# two_tone__1.net
KiCad netlist of a schematic drawn in EAGLE
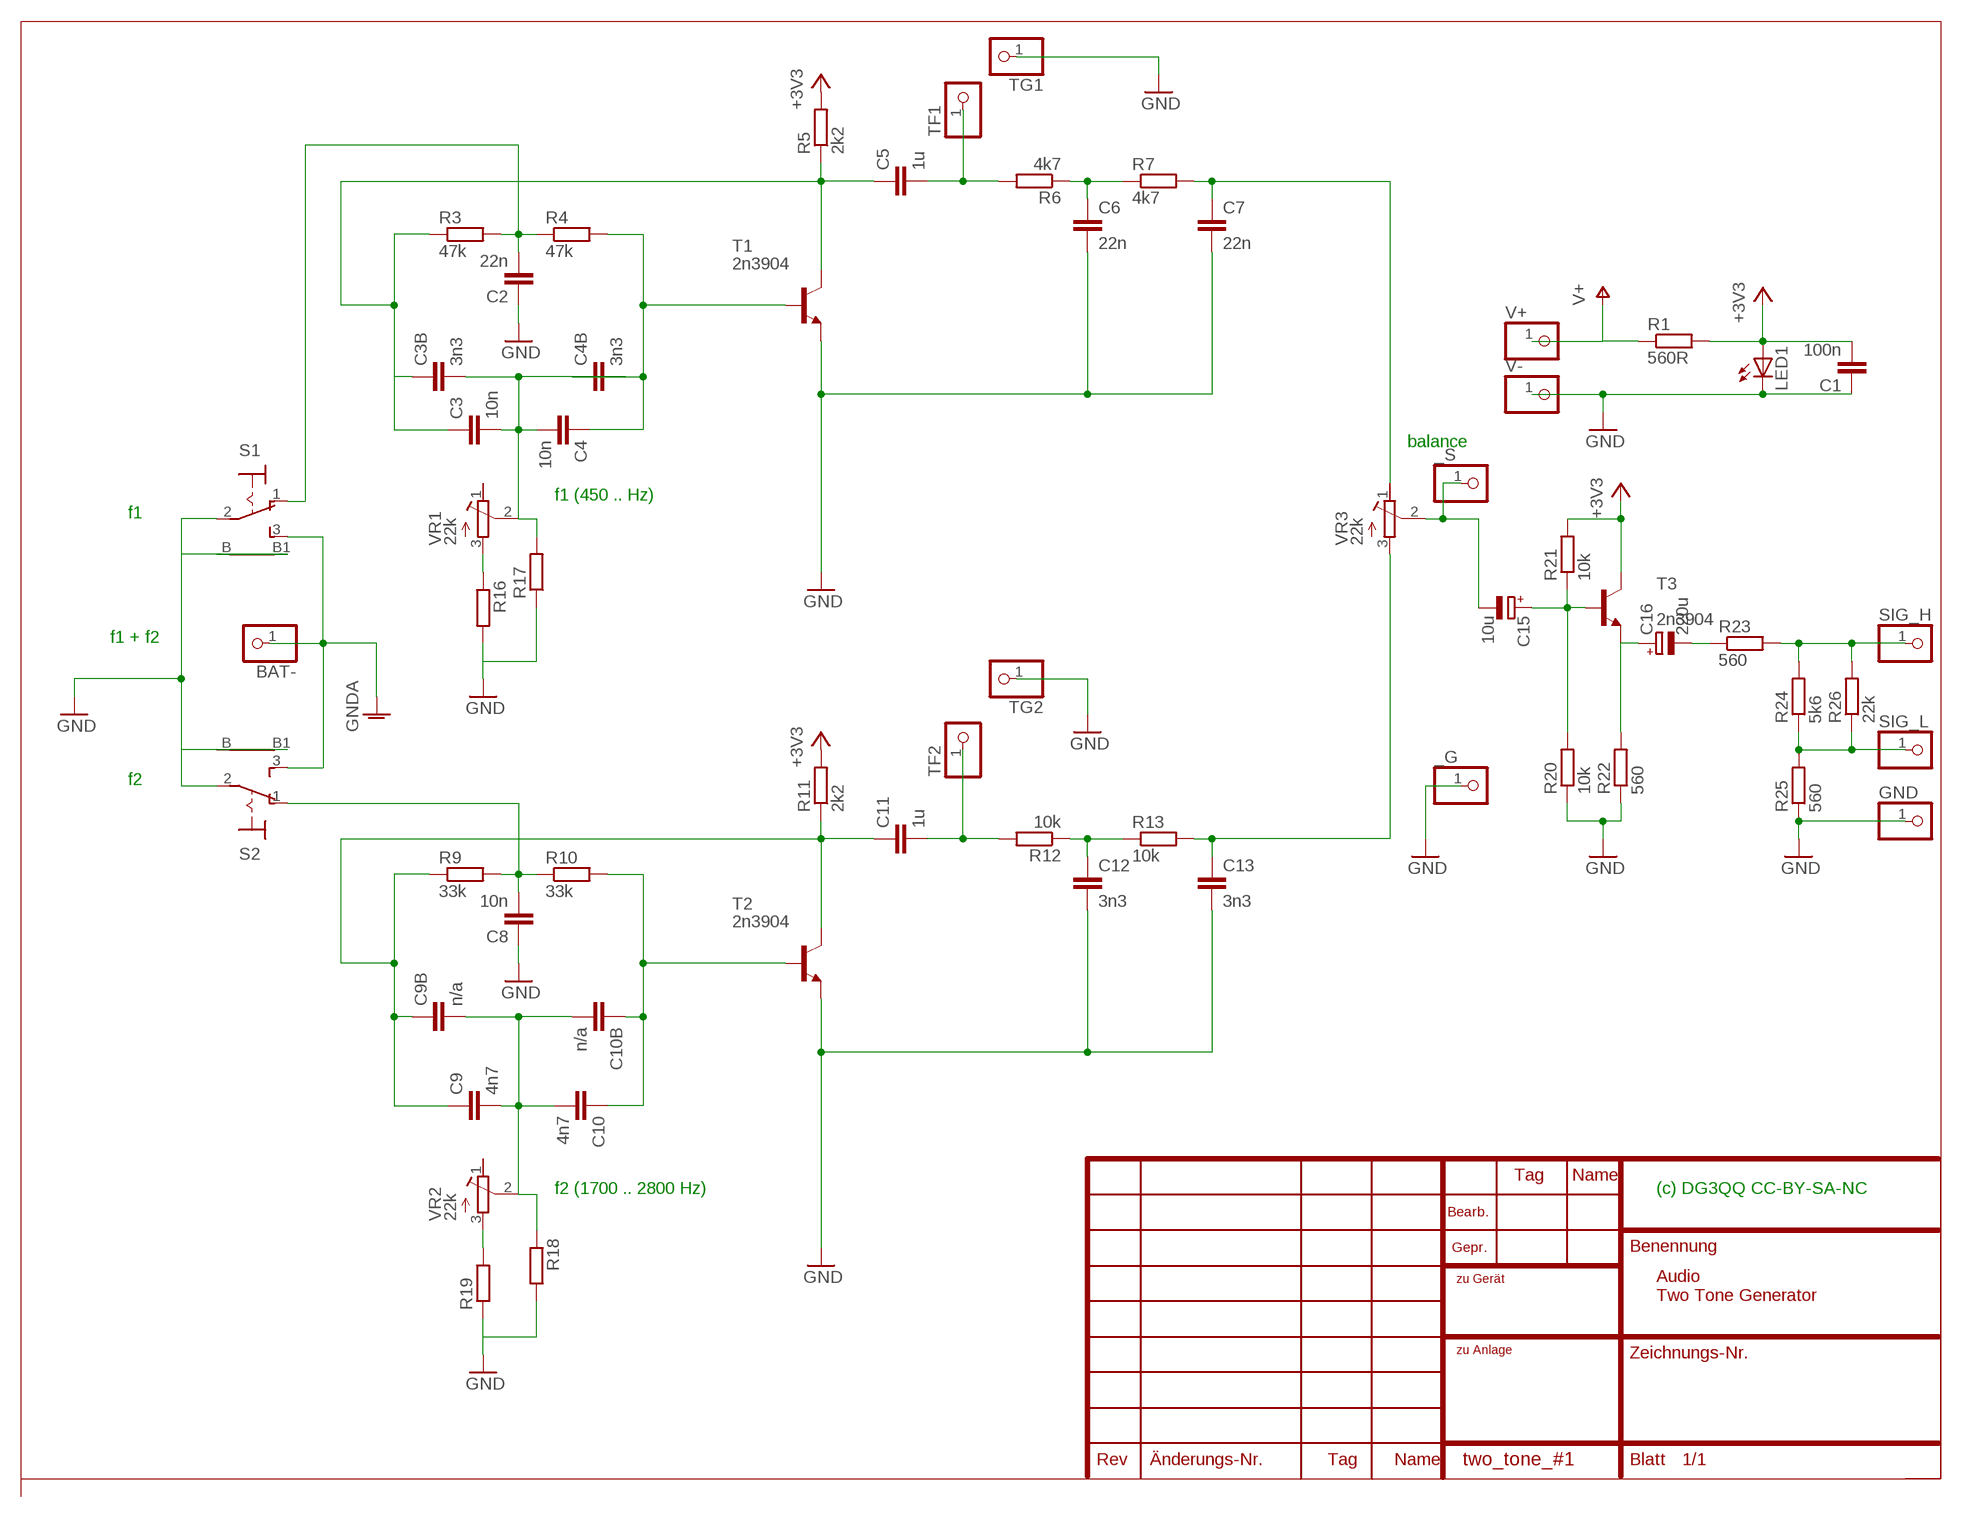
[diagram p0: schematic, sheet 1]

(export (version "E")
  (design (tool "Eeschema 10.0.6"))
  (components
    (comp (ref "BAT-")
      (value "PINHD-1X1")
      (footprint "eagle-import:1X01")
      (libsource (lib "eagle-import") (part "PINHD-1X1"))
    )
    (comp (ref "C1")
      (value "100n")
      (footprint "eagle-import:C025_050-025X075")
      (libsource (lib "eagle-import") (part "C-EU025_050-025X075"))
    )
    (comp (ref "C2")
      (value "22n")
      (footprint "eagle-import:C025_050-025X075")
      (libsource (lib "eagle-import") (part "C-EU025_050-025X075"))
    )
    (comp (ref "C3")
      (value "10n")
      (footprint "eagle-import:C025_050-025X075")
      (libsource (lib "eagle-import") (part "C-EU025_050-025X075"))
    )
    (comp (ref "C3B")
      (value "3n3")
      (footprint "eagle-import:C025_050-025X075")
      (libsource (lib "eagle-import") (part "C-EU025_050-025X075"))
    )
    (comp (ref "C4")
      (value "10n")
      (footprint "eagle-import:C025_050-025X075")
      (libsource (lib "eagle-import") (part "C-EU025_050-025X075"))
    )
    (comp (ref "C4B")
      (value "3n3")
      (footprint "eagle-import:C025_050-025X075")
      (libsource (lib "eagle-import") (part "C-EU025_050-025X075"))
    )
    (comp (ref "C5")
      (value "1u")
      (footprint "eagle-import:C025_050-025X075")
      (libsource (lib "eagle-import") (part "C-EU025_050-025X075"))
    )
    (comp (ref "C6")
      (value "22n")
      (footprint "eagle-import:C025_050-025X075")
      (libsource (lib "eagle-import") (part "C-EU025_050-025X075"))
    )
    (comp (ref "C7")
      (value "22n")
      (footprint "eagle-import:C025_050-025X075")
      (libsource (lib "eagle-import") (part "C-EU025_050-025X075"))
    )
    (comp (ref "C8")
      (value "10n")
      (footprint "eagle-import:C025_050-025X075")
      (libsource (lib "eagle-import") (part "C-EU025_050-025X075"))
    )
    (comp (ref "C9")
      (value "4n7")
      (footprint "eagle-import:C025_050-025X075")
      (libsource (lib "eagle-import") (part "C-EU025_050-025X075"))
    )
    (comp (ref "C9B")
      (value "n/a")
      (footprint "eagle-import:C025_050-025X075")
      (libsource (lib "eagle-import") (part "C-EU025_050-025X075"))
    )
    (comp (ref "C10")
      (value "4n7")
      (footprint "eagle-import:C025_050-025X075")
      (libsource (lib "eagle-import") (part "C-EU025_050-025X075"))
    )
    (comp (ref "C10B")
      (value "n/a")
      (footprint "eagle-import:C025_050-025X075")
      (libsource (lib "eagle-import") (part "C-EU025_050-025X075"))
    )
    (comp (ref "C11")
      (value "1u")
      (footprint "eagle-import:C025_050-025X075")
      (libsource (lib "eagle-import") (part "C-EU025_050-025X075"))
    )
    (comp (ref "C12")
      (value "3n3")
      (footprint "eagle-import:C025_050-025X075")
      (libsource (lib "eagle-import") (part "C-EU025_050-025X075"))
    )
    (comp (ref "C13")
      (value "3n3")
      (footprint "eagle-import:C025_050-025X075")
      (libsource (lib "eagle-import") (part "C-EU025_050-025X075"))
    )
    (comp (ref "C15")
      (value "10u")
      (footprint "eagle-import:E2,5-5")
      (libsource (lib "eagle-import") (part "CPOL-EUE2.5-5"))
    )
    (comp (ref "C16")
      (value "220u")
      (footprint "eagle-import:E5-10,5")
      (libsource (lib "eagle-import") (part "CPOL-EUE5-10.5"))
    )
    (comp (ref "GND")
      (value "PINHD-1X1")
      (footprint "eagle-import:1X01")
      (libsource (lib "eagle-import") (part "PINHD-1X1"))
    )
    (comp (ref "LED1")
      (value "LED3MM")
      (footprint "eagle-import:LED3MM")
      (libsource (lib "eagle-import") (part "LED3MM"))
    )
    (comp (ref "R1")
      (value "560R")
      (footprint "eagle-import:0207_2V")
      (libsource (lib "eagle-import") (part "R-EU_0207/2V"))
    )
    (comp (ref "R3")
      (value "47k")
      (footprint "eagle-import:0207_10")
      (libsource (lib "eagle-import") (part "R-EU_0207/10"))
    )
    (comp (ref "R4")
      (value "47k")
      (footprint "eagle-import:0207_2V")
      (libsource (lib "eagle-import") (part "R-EU_0207/2V"))
    )
    (comp (ref "R5")
      (value "2k2")
      (footprint "eagle-import:0207_2V")
      (libsource (lib "eagle-import") (part "R-EU_0207/2V"))
    )
    (comp (ref "R6")
      (value "4k7")
      (footprint "eagle-import:0207_2V")
      (libsource (lib "eagle-import") (part "R-EU_0207/2V"))
    )
    (comp (ref "R7")
      (value "4k7")
      (footprint "eagle-import:0207_2V")
      (libsource (lib "eagle-import") (part "R-EU_0207/2V"))
    )
    (comp (ref "R9")
      (value "33k")
      (footprint "eagle-import:0207_10")
      (libsource (lib "eagle-import") (part "R-EU_0207/10"))
    )
    (comp (ref "R10")
      (value "33k")
      (footprint "eagle-import:0207_2V")
      (libsource (lib "eagle-import") (part "R-EU_0207/2V"))
    )
    (comp (ref "R11")
      (value "2k2")
      (footprint "eagle-import:0207_2V")
      (libsource (lib "eagle-import") (part "R-EU_0207/2V"))
    )
    (comp (ref "R12")
      (value "10k")
      (footprint "eagle-import:0207_2V")
      (libsource (lib "eagle-import") (part "R-EU_0207/2V"))
    )
    (comp (ref "R13")
      (value "10k")
      (footprint "eagle-import:0207_2V")
      (libsource (lib "eagle-import") (part "R-EU_0207/2V"))
    )
    (comp (ref "R16")
      (value "R-EU_0207/2V")
      (footprint "eagle-import:0207_2V")
      (libsource (lib "eagle-import") (part "R-EU_0207/2V"))
    )
    (comp (ref "R17")
      (value "R-EU_0207/2V")
      (footprint "eagle-import:0207_2V")
      (libsource (lib "eagle-import") (part "R-EU_0207/2V"))
    )
    (comp (ref "R18")
      (value "R-EU_0207/2V")
      (footprint "eagle-import:0207_2V")
      (libsource (lib "eagle-import") (part "R-EU_0207/2V"))
    )
    (comp (ref "R19")
      (value "R-EU_0207/2V")
      (footprint "eagle-import:0207_2V")
      (libsource (lib "eagle-import") (part "R-EU_0207/2V"))
    )
    (comp (ref "R20")
      (value "10k")
      (footprint "eagle-import:0207_2V")
      (libsource (lib "eagle-import") (part "R-EU_0207/2V"))
    )
    (comp (ref "R21")
      (value "10k")
      (footprint "eagle-import:0207_2V")
      (libsource (lib "eagle-import") (part "R-EU_0207/2V"))
    )
    (comp (ref "R22")
      (value "560")
      (footprint "eagle-import:0207_2V")
      (libsource (lib "eagle-import") (part "R-EU_0207/2V"))
    )
    (comp (ref "R23")
      (value "560")
      (footprint "eagle-import:0207_2V")
      (libsource (lib "eagle-import") (part "R-EU_0207/2V"))
    )
    (comp (ref "R24")
      (value "5k6")
      (footprint "eagle-import:0207_2V")
      (libsource (lib "eagle-import") (part "R-EU_0207/2V"))
    )
    (comp (ref "R25")
      (value "560")
      (footprint "eagle-import:0207_2V")
      (libsource (lib "eagle-import") (part "R-EU_0207/2V"))
    )
    (comp (ref "R26")
      (value "22k")
      (footprint "eagle-import:0207_2V")
      (libsource (lib "eagle-import") (part "R-EU_0207/2V"))
    )
    (comp (ref "S1")
      (value "9070-1W")
      (footprint "eagle-import:9070-1W")
      (libsource (lib "eagle-import") (part "9070-1W"))
    )
    (comp (ref "S2")
      (value "9070-1W")
      (footprint "eagle-import:9070-1W")
      (libsource (lib "eagle-import") (part "9070-1W"))
    )
    (comp (ref "SIG_H")
      (value "PINHD-1X1")
      (footprint "eagle-import:1X01")
      (libsource (lib "eagle-import") (part "PINHD-1X1"))
    )
    (comp (ref "SIG_L")
      (value "PINHD-1X1")
      (footprint "eagle-import:1X01")
      (libsource (lib "eagle-import") (part "PINHD-1X1"))
    )
    (comp (ref "T1")
      (value "2n3904")
      (footprint "eagle-import:TO92-EBC")
      (libsource (lib "eagle-import") (part "-NPN-TO92-EBC2N3904"))
    )
    (comp (ref "T2")
      (value "2n3904")
      (footprint "eagle-import:TO92-EBC")
      (libsource (lib "eagle-import") (part "-NPN-TO92-EBC2N3904"))
    )
    (comp (ref "T3")
      (value "2n3904")
      (footprint "eagle-import:TO92-EBC")
      (libsource (lib "eagle-import") (part "-NPN-TO92-EBC2N3904"))
    )
    (comp (ref "TF1")
      (value "PINHD-1X1")
      (footprint "eagle-import:1X01")
      (libsource (lib "eagle-import") (part "PINHD-1X1"))
    )
    (comp (ref "TF2")
      (value "PINHD-1X1")
      (footprint "eagle-import:1X01")
      (libsource (lib "eagle-import") (part "PINHD-1X1"))
    )
    (comp (ref "TG1")
      (value "PINHD-1X1")
      (footprint "eagle-import:1X01")
      (libsource (lib "eagle-import") (part "PINHD-1X1"))
    )
    (comp (ref "TG2")
      (value "PINHD-1X1")
      (footprint "eagle-import:1X01")
      (libsource (lib "eagle-import") (part "PINHD-1X1"))
    )
    (comp (ref "V+")
      (value "PINHD-1X1")
      (footprint "eagle-import:1X01")
      (libsource (lib "eagle-import") (part "PINHD-1X1"))
    )
    (comp (ref "V-")
      (value "PINHD-1X1")
      (footprint "eagle-import:1X01")
      (libsource (lib "eagle-import") (part "PINHD-1X1"))
    )
    (comp (ref "VR1")
      (value "22k")
      (footprint "eagle-import:SPINDLE_414S6")
      (libsource (lib "eagle-import") (part "R-TRIMM_414S6"))
    )
    (comp (ref "VR2")
      (value "22k")
      (footprint "eagle-import:SPINDLE_414S6")
      (libsource (lib "eagle-import") (part "R-TRIMM_414S6"))
    )
    (comp (ref "VR3")
      (value "22k")
      (footprint "eagle-import:SPINDLE_414S6")
      (libsource (lib "eagle-import") (part "R-TRIMM_414S6"))
    )
    (comp (ref "_G")
      (value "PINHD-1X1")
      (footprint "eagle-import:1X01")
      (libsource (lib "eagle-import") (part "PINHD-1X1"))
    )
    (comp (ref "_S")
      (value "PINHD-1X1")
      (footprint "eagle-import:1X01")
      (libsource (lib "eagle-import") (part "PINHD-1X1"))
    )
  )
  (nets
    (net (code "1") (name "+3V3") (class "Default")
      (node (ref "C1") (pin "2") (pinfunction "2_2") (pintype "passive"))
      (node (ref "LED1") (pin "A") (pinfunction "A_A") (pintype "passive"))
      (node (ref "R1") (pin "2") (pinfunction "2_2") (pintype "passive"))
      (node (ref "R11") (pin "2") (pinfunction "2_2") (pintype "passive"))
      (node (ref "R21") (pin "2") (pinfunction "2_2") (pintype "passive"))
      (node (ref "R5") (pin "2") (pinfunction "2_2") (pintype "passive"))
      (node (ref "T3") (pin "C") (pinfunction "C_C") (pintype "passive"))
    )
    (net (code "2") (name "GND") (class "Default")
      (node (ref "C1") (pin "1") (pinfunction "1_1") (pintype "passive"))
      (node (ref "C12") (pin "2") (pinfunction "2_2") (pintype "passive"))
      (node (ref "C13") (pin "2") (pinfunction "2_2") (pintype "passive"))
      (node (ref "C2") (pin "1") (pinfunction "1_1") (pintype "passive"))
      (node (ref "C6") (pin "2") (pinfunction "2_2") (pintype "passive"))
      (node (ref "C7") (pin "2") (pinfunction "2_2") (pintype "passive"))
      (node (ref "C8") (pin "1") (pinfunction "1_1") (pintype "passive"))
      (node (ref "GND") (pin "1") (pinfunction "1_1") (pintype "passive"))
      (node (ref "LED1") (pin "K") (pinfunction "C_K") (pintype "passive"))
      (node (ref "R16") (pin "2") (pinfunction "2_2") (pintype "passive"))
      (node (ref "R17") (pin "1") (pinfunction "1_1") (pintype "passive"))
      (node (ref "R18") (pin "2") (pinfunction "2_2") (pintype "passive"))
      (node (ref "R19") (pin "1") (pinfunction "1_1") (pintype "passive"))
      (node (ref "R20") (pin "1") (pinfunction "1_1") (pintype "passive"))
      (node (ref "R22") (pin "1") (pinfunction "1_1") (pintype "passive"))
      (node (ref "R25") (pin "1") (pinfunction "1_1") (pintype "passive"))
      (node (ref "S1") (pin "2") (pinfunction "P_2") (pintype "passive"))
      (node (ref "S1") (pin "B") (pinfunction "B_B") (pintype "passive"))
      (node (ref "S1") (pin "B1") (pinfunction "B1_B1") (pintype "passive"))
      (node (ref "S2") (pin "2") (pinfunction "P_2") (pintype "passive"))
      (node (ref "S2") (pin "B") (pinfunction "B_B") (pintype "passive"))
      (node (ref "S2") (pin "B1") (pinfunction "B1_B1") (pintype "passive"))
      (node (ref "T1") (pin "E") (pinfunction "E_E") (pintype "passive"))
      (node (ref "T2") (pin "E") (pinfunction "E_E") (pintype "passive"))
      (node (ref "TG1") (pin "1") (pinfunction "1_1") (pintype "passive"))
      (node (ref "TG2") (pin "1") (pinfunction "1_1") (pintype "passive"))
      (node (ref "V-") (pin "1") (pinfunction "1_1") (pintype "passive"))
      (node (ref "_G") (pin "1") (pinfunction "1_1") (pintype "passive"))
    )
    (net (code "3") (name "GNDA") (class "Default")
      (node (ref "BAT-") (pin "1") (pinfunction "1_1") (pintype "passive"))
      (node (ref "S1") (pin "3") (pinfunction "S_3") (pintype "passive"))
      (node (ref "S2") (pin "3") (pinfunction "S_3") (pintype "passive"))
    )
    (net (code "4") (name "Net-(C3-Pad1)") (class "Default")
      (node (ref "C3") (pin "1") (pinfunction "1_1") (pintype "passive"))
      (node (ref "C3B") (pin "1") (pinfunction "1_1") (pintype "passive"))
      (node (ref "C5") (pin "1") (pinfunction "1_1") (pintype "passive"))
      (node (ref "R3") (pin "1") (pinfunction "1_1") (pintype "passive"))
      (node (ref "R5") (pin "1") (pinfunction "1_1") (pintype "passive"))
      (node (ref "T1") (pin "C") (pinfunction "C_C") (pintype "passive"))
    )
    (net (code "5") (name "Net-(C4-Pad1)") (class "Default")
      (node (ref "C4") (pin "1") (pinfunction "1_1") (pintype "passive"))
      (node (ref "C4B") (pin "1") (pinfunction "1_1") (pintype "passive"))
      (node (ref "R4") (pin "2") (pinfunction "2_2") (pintype "passive"))
      (node (ref "T1") (pin "B") (pinfunction "B_B") (pintype "passive"))
    )
    (net (code "6") (name "Net-(C5-Pad2)") (class "Default")
      (node (ref "C5") (pin "2") (pinfunction "2_2") (pintype "passive"))
      (node (ref "R6") (pin "2") (pinfunction "2_2") (pintype "passive"))
      (node (ref "TF1") (pin "1") (pinfunction "1_1") (pintype "passive"))
    )
    (net (code "7") (name "Net-(C6-Pad1)") (class "Default")
      (node (ref "C6") (pin "1") (pinfunction "1_1") (pintype "passive"))
      (node (ref "R6") (pin "1") (pinfunction "1_1") (pintype "passive"))
      (node (ref "R7") (pin "1") (pinfunction "1_1") (pintype "passive"))
    )
    (net (code "8") (name "Net-(C10-Pad1)") (class "Default")
      (node (ref "C10") (pin "1") (pinfunction "1_1") (pintype "passive"))
      (node (ref "C10B") (pin "1") (pinfunction "1_1") (pintype "passive"))
      (node (ref "R10") (pin "2") (pinfunction "2_2") (pintype "passive"))
      (node (ref "T2") (pin "B") (pinfunction "B_B") (pintype "passive"))
    )
    (net (code "9") (name "Net-(C11-Pad1)") (class "Default")
      (node (ref "C11") (pin "1") (pinfunction "1_1") (pintype "passive"))
      (node (ref "C9") (pin "1") (pinfunction "1_1") (pintype "passive"))
      (node (ref "C9B") (pin "1") (pinfunction "1_1") (pintype "passive"))
      (node (ref "R11") (pin "1") (pinfunction "1_1") (pintype "passive"))
      (node (ref "R9") (pin "1") (pinfunction "1_1") (pintype "passive"))
      (node (ref "T2") (pin "C") (pinfunction "C_C") (pintype "passive"))
    )
    (net (code "10") (name "Net-(C11-Pad2)") (class "Default")
      (node (ref "C11") (pin "2") (pinfunction "2_2") (pintype "passive"))
      (node (ref "R12") (pin "2") (pinfunction "2_2") (pintype "passive"))
      (node (ref "TF2") (pin "1") (pinfunction "1_1") (pintype "passive"))
    )
    (net (code "11") (name "Net-(C12-Pad1)") (class "Default")
      (node (ref "C12") (pin "1") (pinfunction "1_1") (pintype "passive"))
      (node (ref "R12") (pin "1") (pinfunction "1_1") (pintype "passive"))
      (node (ref "R13") (pin "1") (pinfunction "1_1") (pintype "passive"))
    )
    (net (code "12") (name "Net-(C15-Pad+)") (class "Default")
      (node (ref "C15") (pin "+") (pinfunction "+_+") (pintype "passive"))
      (node (ref "R20") (pin "2") (pinfunction "2_2") (pintype "passive"))
      (node (ref "R21") (pin "1") (pinfunction "1_1") (pintype "passive"))
      (node (ref "T3") (pin "B") (pinfunction "B_B") (pintype "passive"))
    )
    (net (code "13") (name "Net-(C16-Pad+)") (class "Default")
      (node (ref "C16") (pin "+") (pinfunction "+_+") (pintype "passive"))
      (node (ref "R22") (pin "2") (pinfunction "2_2") (pintype "passive"))
      (node (ref "T3") (pin "E") (pinfunction "E_E") (pintype "passive"))
    )
    (net (code "14") (name "Net-(C16-Pad-)") (class "Default")
      (node (ref "C16") (pin "-") (pinfunction "-_-") (pintype "passive"))
      (node (ref "R23") (pin "1") (pinfunction "1_1") (pintype "passive"))
    )
    (net (code "15") (name "Net-(R23-Pad2)") (class "Default")
      (node (ref "R23") (pin "2") (pinfunction "2_2") (pintype "passive"))
      (node (ref "R24") (pin "2") (pinfunction "2_2") (pintype "passive"))
      (node (ref "R26") (pin "2") (pinfunction "2_2") (pintype "passive"))
      (node (ref "SIG_H") (pin "1") (pinfunction "1_1") (pintype "passive"))
    )
    (net (code "16") (name "Net-(R24-Pad1)") (class "Default")
      (node (ref "R24") (pin "1") (pinfunction "1_1") (pintype "passive"))
      (node (ref "R25") (pin "2") (pinfunction "2_2") (pintype "passive"))
      (node (ref "R26") (pin "1") (pinfunction "1_1") (pintype "passive"))
      (node (ref "SIG_L") (pin "1") (pinfunction "1_1") (pintype "passive"))
    )
    (net (code "17") (name "Net-(S1-O)") (class "Default")
      (node (ref "C2") (pin "2") (pinfunction "2_2") (pintype "passive"))
      (node (ref "R3") (pin "2") (pinfunction "2_2") (pintype "passive"))
      (node (ref "R4") (pin "1") (pinfunction "1_1") (pintype "passive"))
      (node (ref "S1") (pin "1") (pinfunction "O_1") (pintype "passive"))
    )
    (net (code "18") (name "Net-(S2-O)") (class "Default")
      (node (ref "C8") (pin "2") (pinfunction "2_2") (pintype "passive"))
      (node (ref "R10") (pin "1") (pinfunction "1_1") (pintype "passive"))
      (node (ref "R9") (pin "2") (pinfunction "2_2") (pintype "passive"))
      (node (ref "S2") (pin "1") (pinfunction "O_1") (pintype "passive"))
    )
    (net (code "19") (name "Net-(VR1-E)") (class "Default")
      (node (ref "R16") (pin "1") (pinfunction "1_1") (pintype "passive"))
      (node (ref "VR1") (pin "3") (pinfunction "E_3") (pintype "passive"))
    )
    (net (code "20") (name "Net-(VR1-S)") (class "Default")
      (node (ref "C3") (pin "2") (pinfunction "2_2") (pintype "passive"))
      (node (ref "C3B") (pin "2") (pinfunction "2_2") (pintype "passive"))
      (node (ref "C4") (pin "2") (pinfunction "2_2") (pintype "passive"))
      (node (ref "C4B") (pin "2") (pinfunction "2_2") (pintype "passive"))
      (node (ref "R17") (pin "2") (pinfunction "2_2") (pintype "passive"))
      (node (ref "VR1") (pin "2") (pinfunction "S_2") (pintype "passive"))
    )
    (net (code "21") (name "Net-(VR2-E)") (class "Default")
      (node (ref "R19") (pin "2") (pinfunction "2_2") (pintype "passive"))
      (node (ref "VR2") (pin "3") (pinfunction "E_3") (pintype "passive"))
    )
    (net (code "22") (name "Net-(VR2-S)") (class "Default")
      (node (ref "C10") (pin "2") (pinfunction "2_2") (pintype "passive"))
      (node (ref "C10B") (pin "2") (pinfunction "2_2") (pintype "passive"))
      (node (ref "C9") (pin "2") (pinfunction "2_2") (pintype "passive"))
      (node (ref "C9B") (pin "2") (pinfunction "2_2") (pintype "passive"))
      (node (ref "R18") (pin "1") (pinfunction "1_1") (pintype "passive"))
      (node (ref "VR2") (pin "2") (pinfunction "S_2") (pintype "passive"))
    )
    (net (code "23") (name "Net-(VR3-A)") (class "Default")
      (node (ref "C7") (pin "1") (pinfunction "1_1") (pintype "passive"))
      (node (ref "R7") (pin "2") (pinfunction "2_2") (pintype "passive"))
      (node (ref "VR3") (pin "1") (pinfunction "A_1") (pintype "passive"))
    )
    (net (code "24") (name "Net-(VR3-E)") (class "Default")
      (node (ref "C13") (pin "1") (pinfunction "1_1") (pintype "passive"))
      (node (ref "R13") (pin "2") (pinfunction "2_2") (pintype "passive"))
      (node (ref "VR3") (pin "3") (pinfunction "E_3") (pintype "passive"))
    )
    (net (code "25") (name "Net-(VR3-S)") (class "Default")
      (node (ref "C15") (pin "-") (pinfunction "-_-") (pintype "passive"))
      (node (ref "VR3") (pin "2") (pinfunction "S_2") (pintype "passive"))
      (node (ref "_S") (pin "1") (pinfunction "1_1") (pintype "passive"))
    )
    (net (code "26") (name "V+") (class "Default")
      (node (ref "R1") (pin "1") (pinfunction "1_1") (pintype "passive"))
      (node (ref "V+") (pin "1") (pinfunction "1_1") (pintype "passive"))
    )
    (net (code "27") (name "unconnected-(VR1-A-Pad1)") (class "Default")
      (node (ref "VR1") (pin "1") (pinfunction "A_1") (pintype "passive"))
    )
    (net (code "28") (name "unconnected-(VR2-A-Pad1)") (class "Default")
      (node (ref "VR2") (pin "1") (pinfunction "A_1") (pintype "passive"))
    )
  )
)
